# PT_to_ADCs.net
KiCad netlist of a schematic drawn in Altium Designer
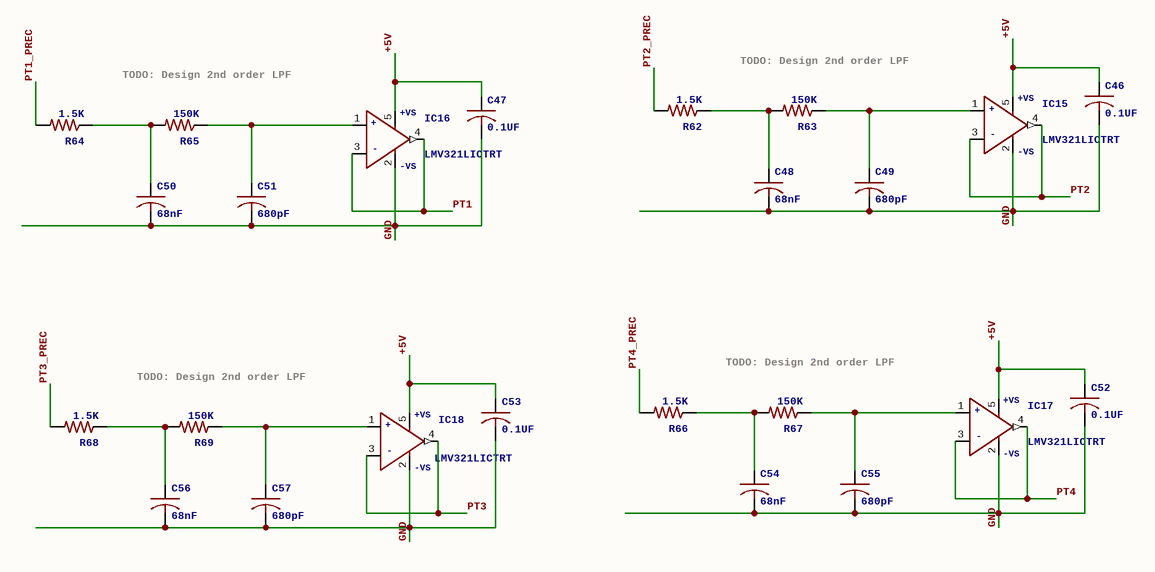
[diagram p0: PT_to_ADCs.SchDoc]

(export (version "E")
  (design (tool "Eeschema 10.0.6"))
  (components
    (comp (ref "C46")
      (value "0.1UF")
      (footprint "CAPCP2012X06N")
      (description "CAPACITOR, American symbol")
      (libsource (lib "rcl") (part "C-USC0805"))
    )
    (comp (ref "C47")
      (value "0.1UF")
      (footprint "CAPCP2012X06N")
      (description "CAPACITOR, American symbol")
      (libsource (lib "rcl") (part "C-USC0805"))
    )
    (comp (ref "C48")
      (value "68nF")
      (footprint "CAPCP2012X06N")
      (description "CAPACITOR, American symbol")
      (libsource (lib "rcl") (part "C-USC0805"))
    )
    (comp (ref "C49")
      (value "680pF")
      (footprint "CAPCP2012X06N")
      (description "CAPACITOR, American symbol")
      (libsource (lib "rcl") (part "C-USC0805"))
    )
    (comp (ref "C50")
      (value "68nF")
      (footprint "CAPCP2012X06N")
      (description "CAPACITOR, American symbol")
      (libsource (lib "rcl") (part "C-USC0805"))
    )
    (comp (ref "C51")
      (value "680pF")
      (footprint "CAPCP2012X06N")
      (description "CAPACITOR, American symbol")
      (libsource (lib "rcl") (part "C-USC0805"))
    )
    (comp (ref "C52")
      (value "0.1UF")
      (footprint "CAPCP2012X06N")
      (description "CAPACITOR, American symbol")
      (libsource (lib "rcl") (part "C-USC0805"))
    )
    (comp (ref "C53")
      (value "0.1UF")
      (footprint "CAPCP2012X06N")
      (description "CAPACITOR, American symbol")
      (libsource (lib "rcl") (part "C-USC0805"))
    )
    (comp (ref "C54")
      (value "68nF")
      (footprint "CAPCP2012X06N")
      (description "CAPACITOR, American symbol")
      (libsource (lib "rcl") (part "C-USC0805"))
    )
    (comp (ref "C55")
      (value "680pF")
      (footprint "CAPCP2012X06N")
      (description "CAPACITOR, American symbol")
      (libsource (lib "rcl") (part "C-USC0805"))
    )
    (comp (ref "C56")
      (value "68nF")
      (footprint "CAPCP2012X06N")
      (description "CAPACITOR, American symbol")
      (libsource (lib "rcl") (part "C-USC0805"))
    )
    (comp (ref "C57")
      (value "680pF")
      (footprint "CAPCP2012X06N")
      (description "CAPACITOR, American symbol")
      (libsource (lib "rcl") (part "C-USC0805"))
    )
    (comp (ref "IC15")
      (value "LMV321LICTRT")
      (footprint "SOT95P245X110-5N")
      (fields
        (field (name "MF") "ALTERA CORPORATION")
        (field (name "MPN") "AD8065ARTZ-REEL7")
        (field (name "+") "+")
        (field (name "-") "-")
        (field (name "+VS") "+VS")
        (field (name "-VS") "-VS")
        (field (name "LIBRARYNAME") "st-microelectronics-extra")
      )
      (libsource (lib "st-microelectronics-extra") (part "LMV321LICTRT"))
    )
    (comp (ref "IC16")
      (value "LMV321LICTRT")
      (footprint "SOT95P245X110-5N")
      (fields
        (field (name "MF") "ALTERA CORPORATION")
        (field (name "MPN") "AD8065ARTZ-REEL7")
        (field (name "+") "+")
        (field (name "-") "-")
        (field (name "+VS") "+VS")
        (field (name "-VS") "-VS")
        (field (name "LIBRARYNAME") "st-microelectronics-extra")
      )
      (libsource (lib "st-microelectronics-extra") (part "LMV321LICTRT"))
    )
    (comp (ref "IC17")
      (value "LMV321LICTRT")
      (footprint "SOT95P245X110-5N")
      (fields
        (field (name "MF") "ALTERA CORPORATION")
        (field (name "MPN") "AD8065ARTZ-REEL7")
        (field (name "+") "+")
        (field (name "-") "-")
        (field (name "+VS") "+VS")
        (field (name "-VS") "-VS")
        (field (name "LIBRARYNAME") "st-microelectronics-extra")
      )
      (libsource (lib "st-microelectronics-extra") (part "LMV321LICTRT"))
    )
    (comp (ref "IC18")
      (value "LMV321LICTRT")
      (footprint "SOT95P245X110-5N")
      (fields
        (field (name "MF") "ALTERA CORPORATION")
        (field (name "MPN") "AD8065ARTZ-REEL7")
        (field (name "+") "+")
        (field (name "-") "-")
        (field (name "+VS") "+VS")
        (field (name "-VS") "-VS")
        (field (name "LIBRARYNAME") "st-microelectronics-extra")
      )
      (libsource (lib "st-microelectronics-extra") (part "LMV321LICTRT"))
    )
    (comp (ref "R62")
      (value "1.5K")
      (footprint "RESC_0805_2012")
      (description "RESISTOR, American symbol")
      (libsource (lib "rcl") (part "R-US_R0805"))
    )
    (comp (ref "R63")
      (value "150K")
      (footprint "RESC_0805_2012")
      (description "RESISTOR, American symbol")
      (libsource (lib "rcl") (part "R-US_R0805"))
    )
    (comp (ref "R64")
      (value "1.5K")
      (footprint "RESC_0805_2012")
      (description "RESISTOR, American symbol")
      (libsource (lib "rcl") (part "R-US_R0805"))
    )
    (comp (ref "R65")
      (value "150K")
      (footprint "RESC_0805_2012")
      (description "RESISTOR, American symbol")
      (libsource (lib "rcl") (part "R-US_R0805"))
    )
    (comp (ref "R66")
      (value "1.5K")
      (footprint "RESC_0805_2012")
      (description "RESISTOR, American symbol")
      (libsource (lib "rcl") (part "R-US_R0805"))
    )
    (comp (ref "R67")
      (value "150K")
      (footprint "RESC_0805_2012")
      (description "RESISTOR, American symbol")
      (libsource (lib "rcl") (part "R-US_R0805"))
    )
    (comp (ref "R68")
      (value "1.5K")
      (footprint "RESC_0805_2012")
      (description "RESISTOR, American symbol")
      (libsource (lib "rcl") (part "R-US_R0805"))
    )
    (comp (ref "R69")
      (value "150K")
      (footprint "RESC_0805_2012")
      (description "RESISTOR, American symbol")
      (libsource (lib "rcl") (part "R-US_R0805"))
    )
  )
  (nets
    (net (code "1") (name "/+5V") (class "Default")
      (node (ref "C46") (pin "1") (pinfunction "1_1") (pintype "passive"))
      (node (ref "C47") (pin "1") (pinfunction "1_1") (pintype "passive"))
      (node (ref "C52") (pin "1") (pinfunction "1_1") (pintype "passive"))
      (node (ref "C53") (pin "1") (pinfunction "1_1") (pintype "passive"))
      (node (ref "IC15") (pin "5") (pinfunction "+VS_5") (pintype "passive"))
      (node (ref "IC16") (pin "5") (pinfunction "+VS_5") (pintype "passive"))
      (node (ref "IC17") (pin "5") (pinfunction "+VS_5") (pintype "passive"))
      (node (ref "IC18") (pin "5") (pinfunction "+VS_5") (pintype "passive"))
    )
    (net (code "2") (name "/GND") (class "Default")
      (node (ref "C46") (pin "2") (pinfunction "2_2") (pintype "passive"))
      (node (ref "C47") (pin "2") (pinfunction "2_2") (pintype "passive"))
      (node (ref "C48") (pin "2") (pinfunction "2_2") (pintype "passive"))
      (node (ref "C49") (pin "2") (pinfunction "2_2") (pintype "passive"))
      (node (ref "C50") (pin "2") (pinfunction "2_2") (pintype "passive"))
      (node (ref "C51") (pin "2") (pinfunction "2_2") (pintype "passive"))
      (node (ref "C52") (pin "2") (pinfunction "2_2") (pintype "passive"))
      (node (ref "C53") (pin "2") (pinfunction "2_2") (pintype "passive"))
      (node (ref "C54") (pin "2") (pinfunction "2_2") (pintype "passive"))
      (node (ref "C55") (pin "2") (pinfunction "2_2") (pintype "passive"))
      (node (ref "C56") (pin "2") (pinfunction "2_2") (pintype "passive"))
      (node (ref "C57") (pin "2") (pinfunction "2_2") (pintype "passive"))
      (node (ref "IC15") (pin "2") (pinfunction "-VS_2") (pintype "passive"))
      (node (ref "IC16") (pin "2") (pinfunction "-VS_2") (pintype "passive"))
      (node (ref "IC17") (pin "2") (pinfunction "-VS_2") (pintype "passive"))
      (node (ref "IC18") (pin "2") (pinfunction "-VS_2") (pintype "passive"))
    )
    (net (code "3") (name "/PT1") (class "Default")
      (node (ref "IC16") (pin "3") (pinfunction "IN-_3") (pintype "passive"))
      (node (ref "IC16") (pin "4") (pinfunction "OUT_4") (pintype "output"))
    )
    (net (code "4") (name "/PT1_PREC") (class "Default")
      (node (ref "R64") (pin "2") (pinfunction "2_2") (pintype "passive"))
    )
    (net (code "5") (name "/PT2") (class "Default")
      (node (ref "IC15") (pin "3") (pinfunction "IN-_3") (pintype "passive"))
      (node (ref "IC15") (pin "4") (pinfunction "OUT_4") (pintype "output"))
    )
    (net (code "6") (name "/PT2_PREC") (class "Default")
      (node (ref "R62") (pin "2") (pinfunction "2_2") (pintype "passive"))
    )
    (net (code "7") (name "/PT3") (class "Default")
      (node (ref "IC18") (pin "3") (pinfunction "IN-_3") (pintype "passive"))
      (node (ref "IC18") (pin "4") (pinfunction "OUT_4") (pintype "output"))
    )
    (net (code "8") (name "/PT3_PREC") (class "Default")
      (node (ref "R68") (pin "2") (pinfunction "2_2") (pintype "passive"))
    )
    (net (code "9") (name "/PT4") (class "Default")
      (node (ref "IC17") (pin "3") (pinfunction "IN-_3") (pintype "passive"))
      (node (ref "IC17") (pin "4") (pinfunction "OUT_4") (pintype "output"))
    )
    (net (code "10") (name "/PT4_PREC") (class "Default")
      (node (ref "R66") (pin "2") (pinfunction "2_2") (pintype "passive"))
    )
    (net (code "11") (name "Net-(C48-Pad1)") (class "Default")
      (node (ref "C48") (pin "1") (pinfunction "1_1") (pintype "passive"))
      (node (ref "R62") (pin "1") (pinfunction "1_1") (pintype "passive"))
      (node (ref "R63") (pin "2") (pinfunction "2_2") (pintype "passive"))
    )
    (net (code "12") (name "Net-(C50-Pad1)") (class "Default")
      (node (ref "C50") (pin "1") (pinfunction "1_1") (pintype "passive"))
      (node (ref "R64") (pin "1") (pinfunction "1_1") (pintype "passive"))
      (node (ref "R65") (pin "2") (pinfunction "2_2") (pintype "passive"))
    )
    (net (code "13") (name "Net-(C54-Pad1)") (class "Default")
      (node (ref "C54") (pin "1") (pinfunction "1_1") (pintype "passive"))
      (node (ref "R66") (pin "1") (pinfunction "1_1") (pintype "passive"))
      (node (ref "R67") (pin "2") (pinfunction "2_2") (pintype "passive"))
    )
    (net (code "14") (name "Net-(C56-Pad1)") (class "Default")
      (node (ref "C56") (pin "1") (pinfunction "1_1") (pintype "passive"))
      (node (ref "R68") (pin "1") (pinfunction "1_1") (pintype "passive"))
      (node (ref "R69") (pin "2") (pinfunction "2_2") (pintype "passive"))
    )
    (net (code "15") (name "Net-(IC15-IN+)") (class "Default")
      (node (ref "C49") (pin "1") (pinfunction "1_1") (pintype "passive"))
      (node (ref "IC15") (pin "1") (pinfunction "IN+_1") (pintype "passive"))
      (node (ref "R63") (pin "1") (pinfunction "1_1") (pintype "passive"))
    )
    (net (code "16") (name "Net-(IC16-IN+)") (class "Default")
      (node (ref "C51") (pin "1") (pinfunction "1_1") (pintype "passive"))
      (node (ref "IC16") (pin "1") (pinfunction "IN+_1") (pintype "passive"))
      (node (ref "R65") (pin "1") (pinfunction "1_1") (pintype "passive"))
    )
    (net (code "17") (name "Net-(IC17-IN+)") (class "Default")
      (node (ref "C55") (pin "1") (pinfunction "1_1") (pintype "passive"))
      (node (ref "IC17") (pin "1") (pinfunction "IN+_1") (pintype "passive"))
      (node (ref "R67") (pin "1") (pinfunction "1_1") (pintype "passive"))
    )
    (net (code "18") (name "Net-(IC18-IN+)") (class "Default")
      (node (ref "C57") (pin "1") (pinfunction "1_1") (pintype "passive"))
      (node (ref "IC18") (pin "1") (pinfunction "IN+_1") (pintype "passive"))
      (node (ref "R69") (pin "1") (pinfunction "1_1") (pintype "passive"))
    )
  )
)
